# 10_-MODEM_CONNECTORS.net
KiCad netlist of a schematic drawn in Altium Designer
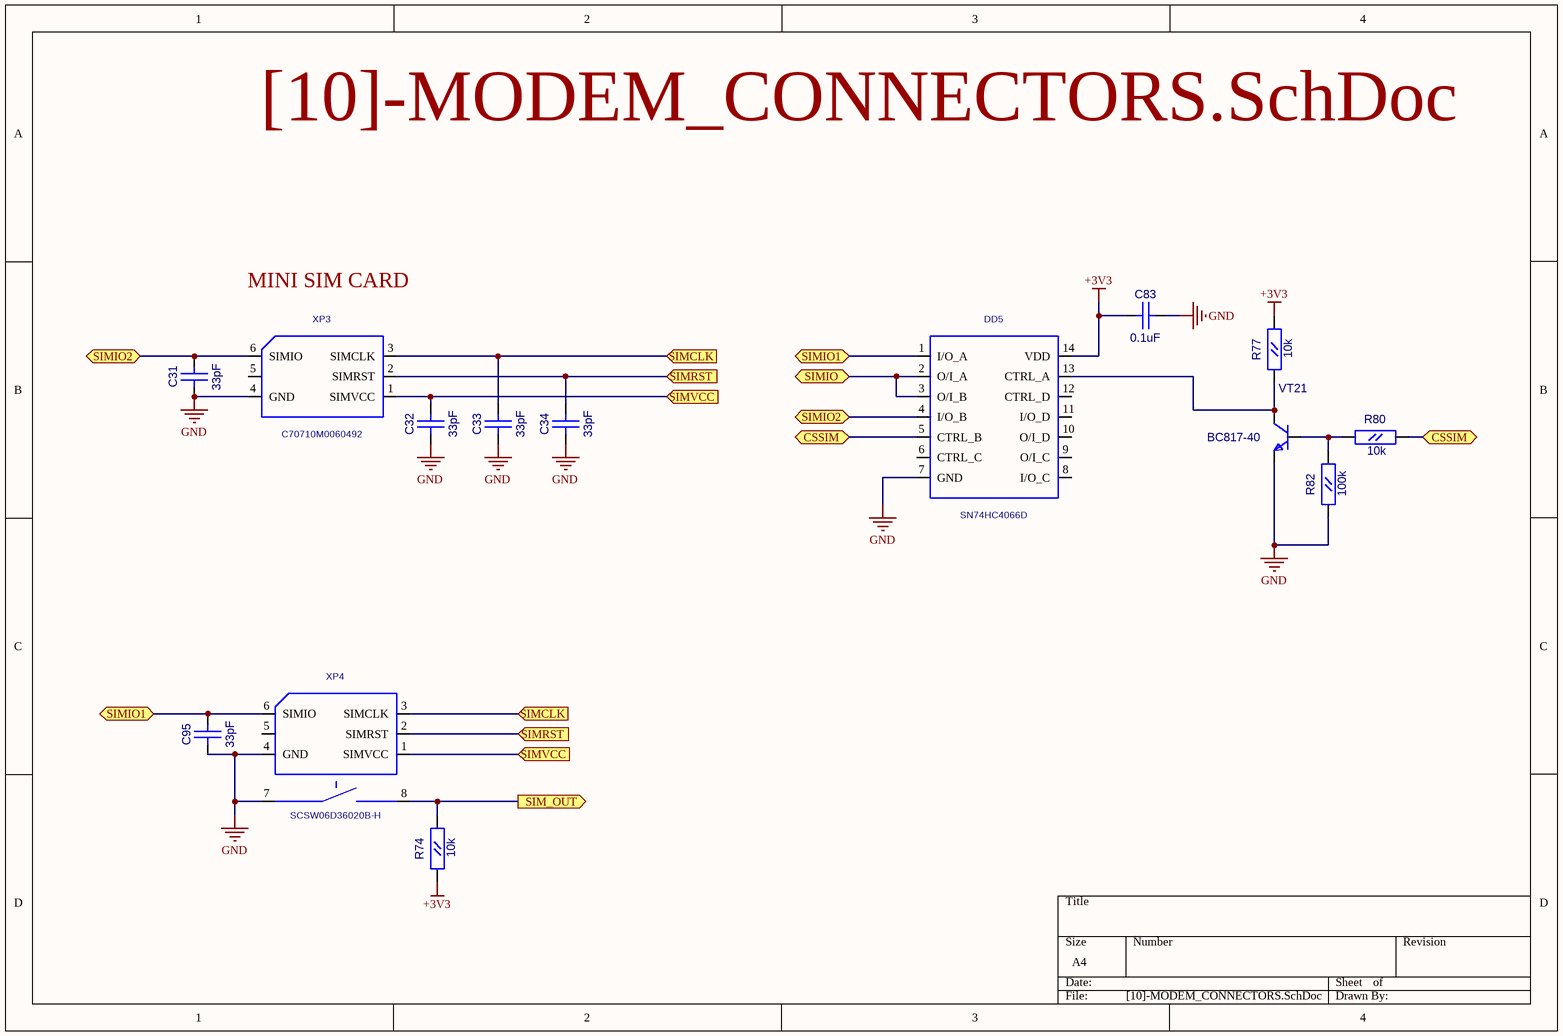
[diagram p0: [10]-MODEM_CONNECTORS.SchDoc]

(export (version "E")
  (design (tool "Eeschema 10.0.6"))
  (components
    (comp (ref "C31")
      (value "33pF")
      (footprint "CC0603")
      (description "CC0603")
      (libsource (lib "gprs_modem_2") (part "CC0603"))
    )
    (comp (ref "C32")
      (value "33pF")
      (footprint "CC0603")
      (description "CC0603")
      (libsource (lib "gprs_modem_2") (part "CC0603"))
    )
    (comp (ref "C33")
      (value "33pF")
      (footprint "CC0603")
      (description "CC0603")
      (libsource (lib "gprs_modem_2") (part "CC0603"))
    )
    (comp (ref "C34")
      (value "33pF")
      (footprint "CC0603")
      (description "CC0603")
      (libsource (lib "gprs_modem_2") (part "CC0603"))
    )
    (comp (ref "C83")
      (value "0.1uF")
      (footprint "CC0603")
      (description "CC0603")
      (libsource (lib "fizik_lib") (part "CC0603"))
    )
    (comp (ref "C95")
      (value "33pF")
      (footprint "CC0603")
      (description "CC0603")
      (libsource (lib "gprs_modem_2") (part "CC0603"))
    )
    (comp (ref "DD5")
      (value "SN74HC4066D")
      (footprint "SO14")
      (libsource (lib "fizik_lib") (part "SN74HC4066D"))
    )
    (comp (ref "R74")
      (value "10k")
      (footprint "RC0603")
      (description "RC0603")
      (libsource (lib "fizik_lib (1)") (part "RC0603"))
    )
    (comp (ref "R77")
      (value "10k")
      (footprint "RC0603")
      (description "RC0603")
      (libsource (lib "fizik_lib") (part "RC0603"))
    )
    (comp (ref "R80")
      (value "10k")
      (footprint "RC0603")
      (description "RC0603")
      (libsource (lib "fizik_lib") (part "RC0603"))
    )
    (comp (ref "R82")
      (value "100k")
      (footprint "RC0603")
      (description "RC0603")
      (libsource (lib "fizik_lib") (part "RC0603"))
    )
    (comp (ref "VT21")
      (value "BC817-40")
      (footprint "SOT-23(123)")
      (description "NPN 500ma transistor")
      (libsource (lib "fizik_lib") (part "BC846BLT1"))
    )
    (comp (ref "XP3")
      (value "C70710M0060492")
      (footprint "SCVW06A25020")
      (description "SCV-W06A25-020")
      (libsource (lib "gprs_modem_2") (part "SCV-W06A25-020"))
    )
    (comp (ref "XP4")
      (value "SCSW06D36020B-H")
      (footprint "SCSW06D36020B-H")
      (libsource (lib "fizik_lib (1)") (part "SCSW06D36020B-H"))
    )
  )
  (nets
    (net (code "1") (name "+3V3") (class "Default")
      (node (ref "C83") (pin "1") (pinfunction "A_1") (pintype "passive"))
      (node (ref "DD5") (pin "14") (pinfunction "VDD_14") (pintype "passive"))
      (node (ref "R74") (pin "1") (pinfunction "A_1") (pintype "passive"))
      (node (ref "R77") (pin "2") (pinfunction "B_2") (pintype "passive"))
    )
    (net (code "2") (name "/CSSIM") (class "Default")
      (node (ref "DD5") (pin "5") (pinfunction "CTRL_B_5") (pintype "passive"))
      (node (ref "R80") (pin "2") (pinfunction "B_2") (pintype "passive"))
    )
    (net (code "3") (name "/SIMCLK") (class "Default")
      (node (ref "C33") (pin "2") (pinfunction "B_2") (pintype "passive"))
      (node (ref "XP3") (pin "3") (pinfunction "SIMCLK_3") (pintype "passive"))
      (node (ref "XP4") (pin "3") (pinfunction "SIMCLK_3") (pintype "passive"))
    )
    (net (code "4") (name "/SIMIO") (class "Default")
      (node (ref "DD5") (pin "2") (pinfunction "O/I_A_2") (pintype "passive"))
      (node (ref "DD5") (pin "3") (pinfunction "O/I_B_3") (pintype "passive"))
    )
    (net (code "5") (name "/SIMIO1") (class "Default")
      (node (ref "C95") (pin "2") (pinfunction "B_2") (pintype "passive"))
      (node (ref "DD5") (pin "1") (pinfunction "I/O_A_1") (pintype "passive"))
      (node (ref "XP4") (pin "6") (pinfunction "SIMIO_6") (pintype "passive"))
    )
    (net (code "6") (name "/SIMIO2") (class "Default")
      (node (ref "C31") (pin "2") (pinfunction "B_2") (pintype "passive"))
      (node (ref "DD5") (pin "4") (pinfunction "I/O_B_4") (pintype "passive"))
      (node (ref "XP3") (pin "6") (pinfunction "SIMIO_6") (pintype "passive"))
    )
    (net (code "7") (name "/SIMRST") (class "Default")
      (node (ref "C34") (pin "2") (pinfunction "B_2") (pintype "passive"))
      (node (ref "XP3") (pin "2") (pinfunction "SIMRST_2") (pintype "passive"))
      (node (ref "XP4") (pin "2") (pinfunction "SIMRST_2") (pintype "passive"))
    )
    (net (code "8") (name "/SIMVCC") (class "Default")
      (node (ref "C32") (pin "2") (pinfunction "B_2") (pintype "passive"))
      (node (ref "XP3") (pin "1") (pinfunction "SIMVCC_1") (pintype "passive"))
      (node (ref "XP4") (pin "1") (pinfunction "SIMVCC_1") (pintype "passive"))
    )
    (net (code "9") (name "/SIM_OUT") (class "Default")
      (node (ref "R74") (pin "2") (pinfunction "B_2") (pintype "passive"))
      (node (ref "XP4") (pin "8") (pintype "passive"))
    )
    (net (code "10") (name "GND") (class "Default")
      (node (ref "C31") (pin "1") (pinfunction "A_1") (pintype "passive"))
      (node (ref "C32") (pin "1") (pinfunction "A_1") (pintype "passive"))
      (node (ref "C33") (pin "1") (pinfunction "A_1") (pintype "passive"))
      (node (ref "C34") (pin "1") (pinfunction "A_1") (pintype "passive"))
      (node (ref "C83") (pin "2") (pinfunction "B_2") (pintype "passive"))
      (node (ref "C95") (pin "1") (pinfunction "A_1") (pintype "passive"))
      (node (ref "DD5") (pin "7") (pinfunction "GND_7") (pintype "passive"))
      (node (ref "R82") (pin "1") (pinfunction "A_1") (pintype "passive"))
      (node (ref "VT21") (pin "2") (pinfunction "E_2") (pintype "passive"))
      (node (ref "XP3") (pin "4") (pinfunction "GND_4") (pintype "passive"))
      (node (ref "XP4") (pin "4") (pinfunction "GND_4") (pintype "passive"))
      (node (ref "XP4") (pin "7") (pintype "passive"))
    )
    (net (code "11") (name "Net-(DD5-CTRL_A)") (class "Default")
      (node (ref "DD5") (pin "13") (pinfunction "CTRL_A_13") (pintype "passive"))
      (node (ref "R77") (pin "1") (pinfunction "A_1") (pintype "passive"))
      (node (ref "VT21") (pin "3") (pinfunction "C_3") (pintype "passive"))
    )
    (net (code "12") (name "Net-(R80-A)") (class "Default")
      (node (ref "R80") (pin "1") (pinfunction "A_1") (pintype "passive"))
      (node (ref "R82") (pin "2") (pinfunction "B_2") (pintype "passive"))
      (node (ref "VT21") (pin "1") (pinfunction "B_1") (pintype "passive"))
    )
    (net (code "13") (name "unconnected-(DD5-CTRL_C-Pad6)") (class "Default")
      (node (ref "DD5") (pin "6") (pinfunction "CTRL_C_6") (pintype "passive"))
    )
    (net (code "14") (name "unconnected-(DD5-CTRL_D-Pad12)") (class "Default")
      (node (ref "DD5") (pin "12") (pinfunction "CTRL_D_12") (pintype "passive"))
    )
    (net (code "15") (name "unconnected-(DD5-I{slash}O_C-Pad8)") (class "Default")
      (node (ref "DD5") (pin "8") (pinfunction "I/O_C_8") (pintype "passive"))
    )
    (net (code "16") (name "unconnected-(DD5-I{slash}O_D-Pad11)") (class "Default")
      (node (ref "DD5") (pin "11") (pinfunction "I/O_D_11") (pintype "passive"))
    )
    (net (code "17") (name "unconnected-(DD5-O{slash}I_C-Pad9)") (class "Default")
      (node (ref "DD5") (pin "9") (pinfunction "O/I_C_9") (pintype "passive"))
    )
    (net (code "18") (name "unconnected-(DD5-O{slash}I_D-Pad10)") (class "Default")
      (node (ref "DD5") (pin "10") (pinfunction "O/I_D_10") (pintype "passive"))
    )
    (net (code "19") (name "unconnected-(XP3-Pad5)") (class "Default")
      (node (ref "XP3") (pin "5") (pintype "passive"))
    )
    (net (code "20") (name "unconnected-(XP4-Pad5)") (class "Default")
      (node (ref "XP4") (pin "5") (pintype "passive"))
    )
  )
)
